# Radii.net
KiCad netlist of a schematic drawn in EAGLE
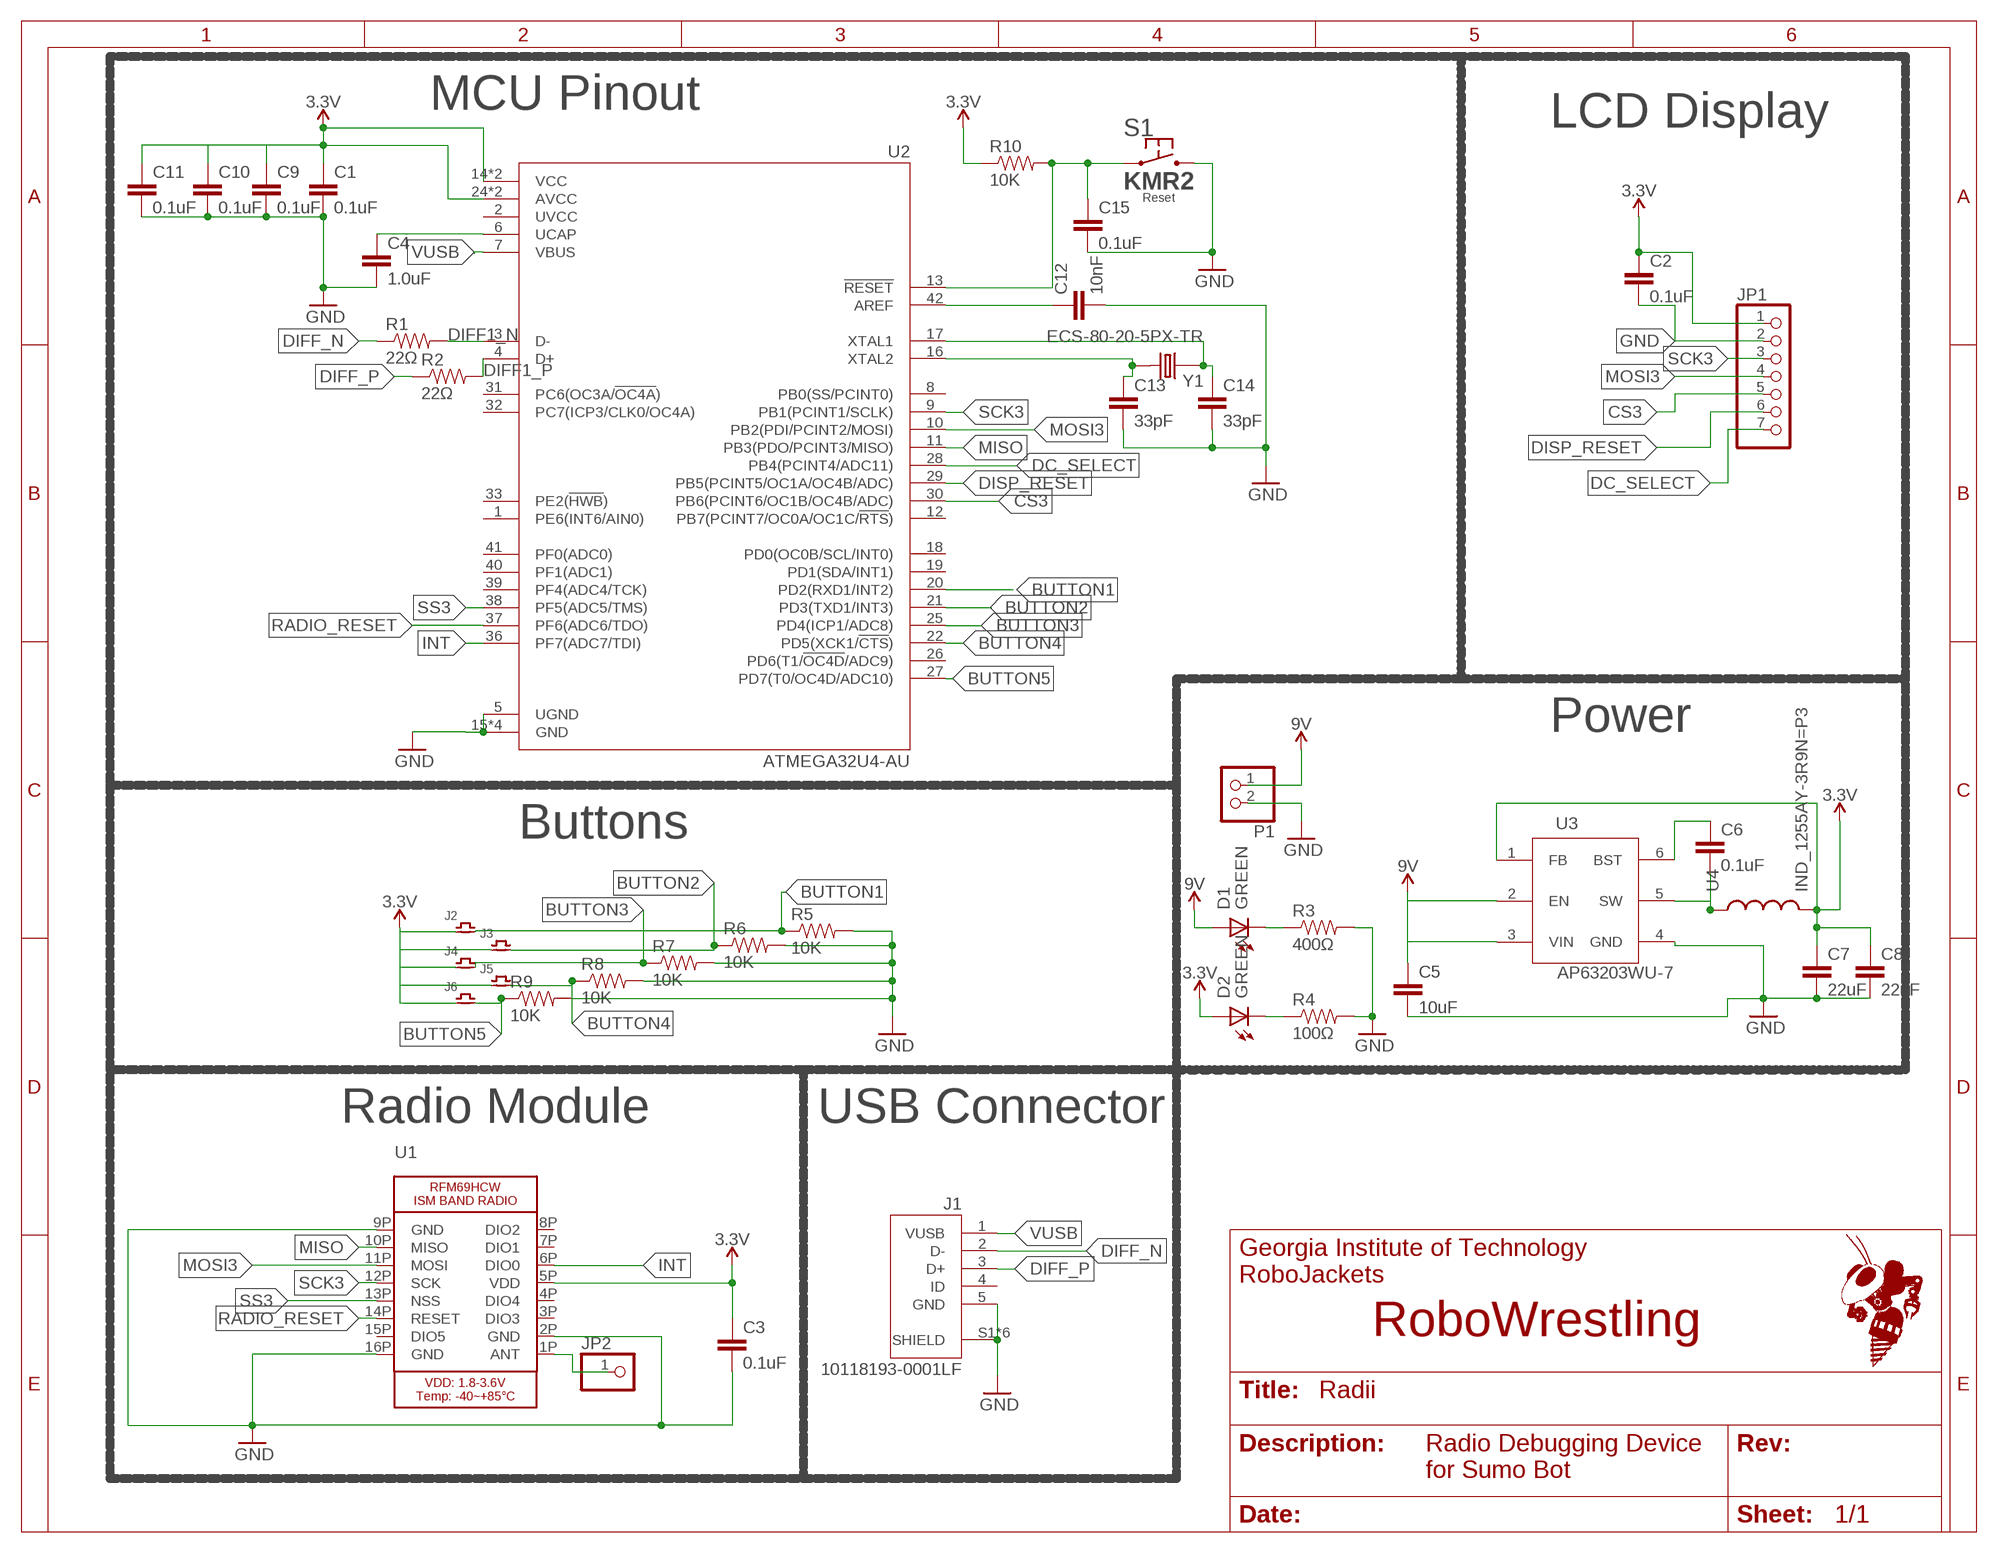
[diagram p0: schematic, sheet 1]

(export (version "E")
  (design (tool "Eeschema 10.0.6"))
  (components
    (comp (ref "C1")
      (value "0.1uF")
      (footprint "eagle-import:0603")
      (libsource (lib "eagle-import") (part "0.1UF-0603-25V-(+80/-20%)"))
    )
    (comp (ref "C2")
      (value "0.1uF")
      (footprint "eagle-import:0603")
      (libsource (lib "eagle-import") (part "0.1UF-0603-25V-(+80/-20%)"))
    )
    (comp (ref "C3")
      (value "0.1uF")
      (footprint "eagle-import:0603")
      (libsource (lib "eagle-import") (part "0.1UF-0603-25V-(+80/-20%)"))
    )
    (comp (ref "C4")
      (value "1.0uF")
      (footprint "eagle-import:0603")
      (libsource (lib "eagle-import") (part "1.0UF-0603-16V-10%"))
    )
    (comp (ref "C5")
      (value "10uF")
      (footprint "eagle-import:0603")
      (libsource (lib "eagle-import") (part "10UF-0603-6.3V-20%"))
    )
    (comp (ref "C6")
      (value "0.1uF")
      (footprint "eagle-import:0603")
      (libsource (lib "eagle-import") (part "0.1UF-0603-25V-(+80/-20%)"))
    )
    (comp (ref "C7")
      (value "22uF")
      (footprint "eagle-import:1210")
      (libsource (lib "eagle-import") (part "22UF-1210-16V-20%"))
    )
    (comp (ref "C8")
      (value "22uF")
      (footprint "eagle-import:1210")
      (libsource (lib "eagle-import") (part "22UF-1210-16V-20%"))
    )
    (comp (ref "C9")
      (value "0.1uF")
      (footprint "eagle-import:0603")
      (libsource (lib "eagle-import") (part "0.1UF-0603-25V-(+80/-20%)"))
    )
    (comp (ref "C10")
      (value "0.1uF")
      (footprint "eagle-import:0603")
      (libsource (lib "eagle-import") (part "0.1UF-0603-25V-(+80/-20%)"))
    )
    (comp (ref "C11")
      (value "0.1uF")
      (footprint "eagle-import:0603")
      (libsource (lib "eagle-import") (part "0.1UF-0603-25V-(+80/-20%)"))
    )
    (comp (ref "C12")
      (value "10nF")
      (footprint "eagle-import:0603")
      (libsource (lib "eagle-import") (part "10NF-0603-50V-10%"))
    )
    (comp (ref "C13")
      (value "33pF")
      (footprint "eagle-import:0603")
      (libsource (lib "eagle-import") (part "33PF-0603-50V-5%"))
    )
    (comp (ref "C14")
      (value "33pF")
      (footprint "eagle-import:0603")
      (libsource (lib "eagle-import") (part "33PF-0603-50V-5%"))
    )
    (comp (ref "C15")
      (value "0.1uF")
      (footprint "eagle-import:0603")
      (libsource (lib "eagle-import") (part "0.1UF-0603-25V-(+80/-20%)"))
    )
    (comp (ref "D1")
      (value "GREEN")
      (footprint "eagle-import:CHIP-LED0603")
      (libsource (lib "eagle-import") (part "LED-SMD"))
    )
    (comp (ref "D2")
      (value "GREEN")
      (footprint "eagle-import:CHIP-LED0603")
      (libsource (lib "eagle-import") (part "LED-SMD"))
    )
    (comp (ref "J1")
      (value "10118193-0001LF")
      (footprint "eagle-import:FCI_10118193-0001LF")
      (fields (field (name "DIGI-KEY_PART_NUMBER") "609-4616-1-ND") (field (name "MF") "Amphenol ICC (FCI)"))
      (libsource (lib "eagle-import") (part "10118193-0001LF"))
    )
    (comp (ref "J2")
      (value "BUTTON")
      (footprint "eagle-import:1X02")
      (libsource (lib "eagle-import") (part "BUTTON"))
    )
    (comp (ref "J3")
      (value "BUTTON")
      (footprint "eagle-import:1X02")
      (libsource (lib "eagle-import") (part "BUTTON"))
    )
    (comp (ref "J4")
      (value "BUTTON")
      (footprint "eagle-import:1X02")
      (libsource (lib "eagle-import") (part "BUTTON"))
    )
    (comp (ref "J5")
      (value "BUTTON")
      (footprint "eagle-import:1X02")
      (libsource (lib "eagle-import") (part "BUTTON"))
    )
    (comp (ref "J6")
      (value "BUTTON")
      (footprint "eagle-import:1X02")
      (libsource (lib "eagle-import") (part "BUTTON"))
    )
    (comp (ref "JP1")
      (value "PINHD-1X7")
      (footprint "eagle-import:1X07")
      (libsource (lib "eagle-import") (part "PINHD-1X7"))
    )
    (comp (ref "JP2")
      (value "PINHD-1X1")
      (footprint "eagle-import:1X01")
      (libsource (lib "eagle-import") (part "PINHD-1X1"))
    )
    (comp (ref "P1")
      (value "JST_2PIN-SMT-RA")
      (footprint "eagle-import:JST-PH-2-SMT-RA")
      (libsource (lib "eagle-import") (part "JST_2PIN-SMT-RA"))
    )
    (comp (ref "R1")
      (value "22Ω")
      (footprint "eagle-import:0603-RES")
      (libsource (lib "eagle-import") (part "22OHM1/10W1%(0603)"))
    )
    (comp (ref "R2")
      (value "22Ω")
      (footprint "eagle-import:0603-RES")
      (libsource (lib "eagle-import") (part "22OHM1/10W1%(0603)"))
    )
    (comp (ref "R3")
      (value "400Ω")
      (footprint "eagle-import:0603-RES")
      (libsource (lib "eagle-import") (part "RESISTOR0603"))
    )
    (comp (ref "R4")
      (value "100Ω")
      (footprint "eagle-import:0603-RES")
      (libsource (lib "eagle-import") (part "RESISTOR0603"))
    )
    (comp (ref "R5")
      (value "10K")
      (footprint "eagle-import:0603-RES")
      (libsource (lib "eagle-import") (part "10KOHM-1/10W-1%(0603)0603"))
    )
    (comp (ref "R6")
      (value "10K")
      (footprint "eagle-import:0603-RES")
      (libsource (lib "eagle-import") (part "10KOHM-1/10W-1%(0603)0603"))
    )
    (comp (ref "R7")
      (value "10K")
      (footprint "eagle-import:0603-RES")
      (libsource (lib "eagle-import") (part "10KOHM-1/10W-1%(0603)0603"))
    )
    (comp (ref "R8")
      (value "10K")
      (footprint "eagle-import:0603-RES")
      (libsource (lib "eagle-import") (part "10KOHM-1/10W-1%(0603)0603"))
    )
    (comp (ref "R9")
      (value "10K")
      (footprint "eagle-import:0603-RES")
      (libsource (lib "eagle-import") (part "10KOHM-1/10W-1%(0603)0603"))
    )
    (comp (ref "R10")
      (value "10K")
      (footprint "eagle-import:0603-RES")
      (libsource (lib "eagle-import") (part "10KOHM-1/10W-1%(0603)0603"))
    )
    (comp (ref "S1")
      (value "KMR2")
      (footprint "eagle-import:KMR2")
      (fields (field (name "FUNCTION") "Reset"))
      (libsource (lib "eagle-import") (part "KMR2"))
    )
    (comp (ref "U1")
      (value "RFM69HCW_SMT")
      (footprint "eagle-import:RFMHCW_SMT")
      (libsource (lib "eagle-import") (part "RFM69HCW_SMT"))
    )
    (comp (ref "U2")
      (value "ATMEGA32U4-AU")
      (footprint "eagle-import:QFP80P1200X1200X120-44N")
      (fields (field (name "MF") "Microchip") (field (name "MP") "ATMEGA32U4-AUR"))
      (libsource (lib "eagle-import") (part "ATMEGA32U4-AUR"))
    )
    (comp (ref "U3")
      (value "AP63203WU-7")
      (footprint "eagle-import:POWERREG")
      (libsource (lib "eagle-import") (part "AP63203WU-7"))
    )
    (comp (ref "U4")
      (value "IND_1255AY-3R9N=P3")
      (footprint "eagle-import:IND_1255AY-3R9N=P3")
      (libsource (lib "eagle-import") (part "IND_1255AY-3R9N=P3"))
    )
    (comp (ref "Y1")
      (value "ECS-80-20-5PX-TR")
      (footprint "eagle-import:XTAL_ECS-80-20-5PX-TR")
      (fields
        (field (name "DIGI-KEY_PART_NUMBER") "XC1271CT-ND")
        (field (name "MF") "ECS Inc.")
        (field (name "MP") "ECS-80-18-5PX-TR")
      )
      (libsource (lib "eagle-import") (part "ECS-80-20-5PX-TR"))
    )
  )
  (nets
    (net (code "1") (name "/DIFF1_N") (class "Default")
      (node (ref "R1") (pin "2") (pinfunction "2_2") (pintype "passive"))
      (node (ref "U2") (pin "3") (pinfunction "D-_3") (pintype "bidirectional"))
    )
    (net (code "2") (name "/DIFF1_P") (class "Default")
      (node (ref "R2") (pin "2") (pinfunction "2_2") (pintype "passive"))
      (node (ref "U2") (pin "4") (pinfunction "D+_4") (pintype "bidirectional"))
    )
    (net (code "3") (name "/UVCC") (class "Default")
      (node (ref "U2") (pin "2") (pinfunction "UVCC_2") (pintype "power_in"))
    )
    (net (code "4") (name "3.3V") (class "Default")
      (node (ref "C1") (pin "1") (pinfunction "1_1") (pintype "passive"))
      (node (ref "C10") (pin "1") (pinfunction "1_1") (pintype "passive"))
      (node (ref "C11") (pin "1") (pinfunction "1_1") (pintype "passive"))
      (node (ref "C2") (pin "1") (pinfunction "1_1") (pintype "passive"))
      (node (ref "C3") (pin "1") (pinfunction "1_1") (pintype "passive"))
      (node (ref "C7") (pin "1") (pinfunction "1_1") (pintype "passive"))
      (node (ref "C8") (pin "1") (pinfunction "1_1") (pintype "passive"))
      (node (ref "C9") (pin "1") (pinfunction "1_1") (pintype "passive"))
      (node (ref "D2") (pin "A") (pinfunction "A_A") (pintype "passive"))
      (node (ref "J2") (pin "1") (pinfunction "P$1_1") (pintype "bidirectional"))
      (node (ref "J3") (pin "1") (pinfunction "P$1_1") (pintype "bidirectional"))
      (node (ref "J4") (pin "1") (pinfunction "P$1_1") (pintype "bidirectional"))
      (node (ref "J5") (pin "1") (pinfunction "P$1_1") (pintype "bidirectional"))
      (node (ref "J6") (pin "1") (pinfunction "P$1_1") (pintype "bidirectional"))
      (node (ref "JP1") (pin "1") (pinfunction "1_1") (pintype "passive"))
      (node (ref "R10") (pin "1") (pinfunction "1_1") (pintype "passive"))
      (node (ref "U1") (pin "5P") (pinfunction "VDD_5P") (pintype "power_in"))
      (node (ref "U2") (pin "14") (pinfunction "VCC_14") (pintype "power_in"))
      (node (ref "U2") (pin "24") (pinfunction "AVCC_24") (pintype "power_in"))
      (node (ref "U2") (pin "34") (pinfunction "VCC_34") (pintype "power_in"))
      (node (ref "U2") (pin "44") (pinfunction "AVCC_44") (pintype "power_in"))
      (node (ref "U3") (pin "1") (pinfunction "FB_1") (pintype "bidirectional"))
      (node (ref "U4") (pin "2") (pinfunction "2_2") (pintype "passive"))
    )
    (net (code "5") (name "9V") (class "Default")
      (node (ref "C5") (pin "1") (pinfunction "1_1") (pintype "passive"))
      (node (ref "D1") (pin "A") (pinfunction "A_A") (pintype "passive"))
      (node (ref "P1") (pin "1") (pinfunction "2_1") (pintype "passive"))
      (node (ref "U3") (pin "2") (pinfunction "EN_2") (pintype "bidirectional"))
      (node (ref "U3") (pin "3") (pinfunction "VIN_3") (pintype "bidirectional"))
    )
    (net (code "6") (name "BUTTON1") (class "Default")
      (node (ref "J2") (pin "2") (pinfunction "P$2_2") (pintype "bidirectional"))
      (node (ref "R5") (pin "1") (pinfunction "1_1") (pintype "passive"))
      (node (ref "U2") (pin "20") (pinfunction "PD2(RXD1/INT2)_20") (pintype "bidirectional"))
    )
    (net (code "7") (name "BUTTON2") (class "Default")
      (node (ref "J3") (pin "2") (pinfunction "P$2_2") (pintype "bidirectional"))
      (node (ref "R6") (pin "1") (pinfunction "1_1") (pintype "passive"))
      (node (ref "U2") (pin "21") (pinfunction "PD3(TXD1/INT3)_21") (pintype "bidirectional"))
    )
    (net (code "8") (name "BUTTON3") (class "Default")
      (node (ref "J4") (pin "2") (pinfunction "P$2_2") (pintype "bidirectional"))
      (node (ref "R7") (pin "1") (pinfunction "1_1") (pintype "passive"))
      (node (ref "U2") (pin "25") (pinfunction "PD4(ICP1/ADC8)_25") (pintype "bidirectional"))
    )
    (net (code "9") (name "BUTTON4") (class "Default")
      (node (ref "J5") (pin "2") (pinfunction "P$2_2") (pintype "bidirectional"))
      (node (ref "R8") (pin "1") (pinfunction "1_1") (pintype "passive"))
      (node (ref "U2") (pin "22") (pinfunction "PD5(XCK1/~{CTS})_22") (pintype "bidirectional"))
    )
    (net (code "10") (name "BUTTON5") (class "Default")
      (node (ref "J6") (pin "2") (pinfunction "P$2_2") (pintype "bidirectional"))
      (node (ref "R9") (pin "1") (pinfunction "1_1") (pintype "passive"))
      (node (ref "U2") (pin "27") (pinfunction "PD7(T0/OC4D/ADC10)_27") (pintype "bidirectional"))
    )
    (net (code "11") (name "CS3") (class "Default")
      (node (ref "JP1") (pin "5") (pinfunction "5_5") (pintype "passive"))
      (node (ref "U2") (pin "30") (pinfunction "PB6(PCINT6/OC1B/OC4B/ADC)_30") (pintype "bidirectional"))
    )
    (net (code "12") (name "DC_SELECT") (class "Default")
      (node (ref "JP1") (pin "7") (pinfunction "7_7") (pintype "passive"))
      (node (ref "U2") (pin "28") (pinfunction "PB4(PCINT4/ADC11)_28") (pintype "bidirectional"))
    )
    (net (code "13") (name "DIFF_N") (class "Default")
      (node (ref "J1") (pin "2") (pinfunction "D-_2") (pintype "passive"))
      (node (ref "R1") (pin "1") (pinfunction "1_1") (pintype "passive"))
    )
    (net (code "14") (name "DIFF_P") (class "Default")
      (node (ref "J1") (pin "3") (pinfunction "D+_3") (pintype "passive"))
      (node (ref "R2") (pin "1") (pinfunction "1_1") (pintype "passive"))
    )
    (net (code "15") (name "DISP_RESET") (class "Default")
      (node (ref "JP1") (pin "6") (pinfunction "6_6") (pintype "passive"))
      (node (ref "U2") (pin "29") (pinfunction "PB5(PCINT5/OC1A/OC4B/ADC)_29") (pintype "bidirectional"))
    )
    (net (code "16") (name "GND") (class "Default")
      (node (ref "C1") (pin "2") (pinfunction "2_2") (pintype "passive"))
      (node (ref "C10") (pin "2") (pinfunction "2_2") (pintype "passive"))
      (node (ref "C11") (pin "2") (pinfunction "2_2") (pintype "passive"))
      (node (ref "C12") (pin "2") (pinfunction "2_2") (pintype "passive"))
      (node (ref "C13") (pin "2") (pinfunction "2_2") (pintype "passive"))
      (node (ref "C14") (pin "2") (pinfunction "2_2") (pintype "passive"))
      (node (ref "C15") (pin "2") (pinfunction "2_2") (pintype "passive"))
      (node (ref "C2") (pin "2") (pinfunction "2_2") (pintype "passive"))
      (node (ref "C3") (pin "2") (pinfunction "2_2") (pintype "passive"))
      (node (ref "C4") (pin "2") (pinfunction "2_2") (pintype "passive"))
      (node (ref "C5") (pin "2") (pinfunction "2_2") (pintype "passive"))
      (node (ref "C7") (pin "2") (pinfunction "2_2") (pintype "passive"))
      (node (ref "C8") (pin "2") (pinfunction "2_2") (pintype "passive"))
      (node (ref "C9") (pin "2") (pinfunction "2_2") (pintype "passive"))
      (node (ref "J1") (pin "5") (pinfunction "GND_5") (pintype "passive"))
      (node (ref "J1") (pin "S1") (pinfunction "SHIELD_S1") (pintype "passive"))
      (node (ref "J1") (pin "S2") (pinfunction "SHIELD_S2") (pintype "passive"))
      (node (ref "J1") (pin "S3") (pinfunction "SHIELD_S3") (pintype "passive"))
      (node (ref "J1") (pin "S4") (pinfunction "SHIELD_S4") (pintype "passive"))
      (node (ref "J1") (pin "S5") (pinfunction "SHIELD_S5") (pintype "passive"))
      (node (ref "J1") (pin "S6") (pinfunction "SHIELD_S6") (pintype "passive"))
      (node (ref "JP1") (pin "2") (pinfunction "2_2") (pintype "passive"))
      (node (ref "P1") (pin "2") (pinfunction "1_2") (pintype "passive"))
      (node (ref "R3") (pin "2") (pinfunction "2_2") (pintype "passive"))
      (node (ref "R4") (pin "2") (pinfunction "2_2") (pintype "passive"))
      (node (ref "R5") (pin "2") (pinfunction "2_2") (pintype "passive"))
      (node (ref "R6") (pin "2") (pinfunction "2_2") (pintype "passive"))
      (node (ref "R7") (pin "2") (pinfunction "2_2") (pintype "passive"))
      (node (ref "R8") (pin "2") (pinfunction "2_2") (pintype "passive"))
      (node (ref "R9") (pin "2") (pinfunction "2_2") (pintype "passive"))
      (node (ref "S1") (pin "2.1") (pinfunction "2_2.1") (pintype "passive"))
      (node (ref "S1") (pin "2.2") (pinfunction "2_2.2") (pintype "passive"))
      (node (ref "U1") (pin "16P") (pinfunction "GND_16P") (pintype "power_in"))
      (node (ref "U1") (pin "2P") (pinfunction "GND_2P") (pintype "power_in"))
      (node (ref "U1") (pin "9P") (pinfunction "GND_9P") (pintype "power_in"))
      (node (ref "U2") (pin "15") (pinfunction "GND_15") (pintype "power_in"))
      (node (ref "U2") (pin "23") (pinfunction "GND_23") (pintype "power_in"))
      (node (ref "U2") (pin "35") (pinfunction "GND_35") (pintype "power_in"))
      (node (ref "U2") (pin "43") (pinfunction "GND_43") (pintype "power_in"))
      (node (ref "U2") (pin "5") (pinfunction "UGND_5") (pintype "power_in"))
      (node (ref "U3") (pin "4") (pinfunction "GND_4") (pintype "bidirectional"))
    )
    (net (code "17") (name "INT") (class "Default")
      (node (ref "U1") (pin "6P") (pinfunction "DIO0_6P") (pintype "bidirectional"))
      (node (ref "U2") (pin "36") (pinfunction "PF7(ADC7/TDI)_36") (pintype "bidirectional"))
    )
    (net (code "18") (name "MISO") (class "Default")
      (node (ref "U1") (pin "10P") (pinfunction "MISO_10P") (pintype "output"))
      (node (ref "U2") (pin "11") (pinfunction "PB3(PDO/PCINT3/MISO)_11") (pintype "bidirectional"))
    )
    (net (code "19") (name "MOSI3") (class "Default")
      (node (ref "JP1") (pin "4") (pinfunction "4_4") (pintype "passive"))
      (node (ref "U1") (pin "11P") (pinfunction "MOSI_11P") (pintype "input"))
      (node (ref "U2") (pin "10") (pinfunction "PB2(PDI/PCINT2/MOSI)_10") (pintype "bidirectional"))
    )
    (net (code "20") (name "Net-(D1-K)") (class "Default")
      (node (ref "D1") (pin "C") (pinfunction "K_C") (pintype "passive"))
      (node (ref "R3") (pin "1") (pinfunction "1_1") (pintype "passive"))
    )
    (net (code "21") (name "Net-(D2-K)") (class "Default")
      (node (ref "D2") (pin "C") (pinfunction "K_C") (pintype "passive"))
      (node (ref "R4") (pin "1") (pinfunction "1_1") (pintype "passive"))
    )
    (net (code "22") (name "Net-(U1-ANT)") (class "Default")
      (node (ref "JP2") (pin "1") (pinfunction "1_1") (pintype "passive"))
      (node (ref "U1") (pin "1P") (pinfunction "ANT_1P") (pintype "bidirectional"))
    )
    (net (code "23") (name "Net-(U2-AREF)") (class "Default")
      (node (ref "C12") (pin "1") (pinfunction "1_1") (pintype "passive"))
      (node (ref "U2") (pin "42") (pinfunction "AREF_42") (pintype "input"))
    )
    (net (code "24") (name "Net-(U2-UCAP)") (class "Default")
      (node (ref "C4") (pin "1") (pinfunction "1_1") (pintype "passive"))
      (node (ref "U2") (pin "6") (pinfunction "UCAP_6") (pintype "power_in"))
    )
    (net (code "25") (name "Net-(U2-XTAL1)") (class "Default")
      (node (ref "C14") (pin "1") (pinfunction "1_1") (pintype "passive"))
      (node (ref "U2") (pin "17") (pinfunction "XTAL1_17") (pintype "input"))
      (node (ref "Y1") (pin "1") (pinfunction "1_1") (pintype "passive"))
    )
    (net (code "26") (name "Net-(U2-XTAL2)") (class "Default")
      (node (ref "C13") (pin "1") (pinfunction "1_1") (pintype "passive"))
      (node (ref "U2") (pin "16") (pinfunction "XTAL2_16") (pintype "output"))
      (node (ref "Y1") (pin "2") (pinfunction "2_2") (pintype "passive"))
    )
    (net (code "27") (name "Net-(U2-~{RESET})") (class "Default")
      (node (ref "C15") (pin "1") (pinfunction "1_1") (pintype "passive"))
      (node (ref "R10") (pin "2") (pinfunction "2_2") (pintype "passive"))
      (node (ref "S1") (pin "1.1") (pinfunction "1_1.1") (pintype "passive"))
      (node (ref "S1") (pin "1.2") (pinfunction "1_1.2") (pintype "passive"))
      (node (ref "U2") (pin "13") (pinfunction "~{RESET}_13") (pintype "input"))
    )
    (net (code "28") (name "Net-(U3-BST)") (class "Default")
      (node (ref "C6") (pin "1") (pinfunction "1_1") (pintype "passive"))
      (node (ref "U3") (pin "6") (pinfunction "BST_6") (pintype "bidirectional"))
    )
    (net (code "29") (name "Net-(U3-SW)") (class "Default")
      (node (ref "C6") (pin "2") (pinfunction "2_2") (pintype "passive"))
      (node (ref "U3") (pin "5") (pinfunction "SW_5") (pintype "bidirectional"))
      (node (ref "U4") (pin "1") (pinfunction "1_1") (pintype "passive"))
    )
    (net (code "30") (name "RADIO_RESET") (class "Default")
      (node (ref "U1") (pin "14P") (pinfunction "RESET_14P") (pintype "input"))
      (node (ref "U2") (pin "37") (pinfunction "PF6(ADC6/TDO)_37") (pintype "bidirectional"))
    )
    (net (code "31") (name "SCK3") (class "Default")
      (node (ref "JP1") (pin "3") (pinfunction "3_3") (pintype "passive"))
      (node (ref "U1") (pin "12P") (pinfunction "SCK_12P") (pintype "input"))
      (node (ref "U2") (pin "9") (pinfunction "PB1(PCINT1/SCLK)_9") (pintype "bidirectional"))
    )
    (net (code "32") (name "SS3") (class "Default")
      (node (ref "U1") (pin "13P") (pinfunction "NSS_13P") (pintype "input"))
      (node (ref "U2") (pin "38") (pinfunction "PF5(ADC5/TMS)_38") (pintype "bidirectional"))
    )
    (net (code "33") (name "VUSB") (class "Default")
      (node (ref "J1") (pin "1") (pinfunction "VUSB_1") (pintype "passive"))
      (node (ref "U2") (pin "7") (pinfunction "VBUS_7") (pintype "power_in"))
    )
    (net (code "34") (name "unconnected-(J1-ID-Pad4)") (class "Default")
      (node (ref "J1") (pin "4") (pinfunction "ID_4") (pintype "passive"))
    )
    (net (code "35") (name "unconnected-(U1-DIO1-Pad7P)") (class "Default")
      (node (ref "U1") (pin "7P") (pinfunction "DIO1_7P") (pintype "bidirectional"))
    )
    (net (code "36") (name "unconnected-(U1-DIO2-Pad8P)") (class "Default")
      (node (ref "U1") (pin "8P") (pinfunction "DIO2_8P") (pintype "bidirectional"))
    )
    (net (code "37") (name "unconnected-(U1-DIO3-Pad3P)") (class "Default")
      (node (ref "U1") (pin "3P") (pinfunction "DIO3_3P") (pintype "bidirectional"))
    )
    (net (code "38") (name "unconnected-(U1-DIO4-Pad4P)") (class "Default")
      (node (ref "U1") (pin "4P") (pinfunction "DIO4_4P") (pintype "bidirectional"))
    )
    (net (code "39") (name "unconnected-(U1-DIO5-Pad15P)") (class "Default")
      (node (ref "U1") (pin "15P") (pinfunction "DIO5_15P") (pintype "bidirectional"))
    )
    (net (code "40") (name "unconnected-(U2-PB0(SS{slash}PCINT0)-Pad8)") (class "Default")
      (node (ref "U2") (pin "8") (pinfunction "PB0(SS/PCINT0)_8") (pintype "bidirectional"))
    )
    (net (code "41") (name "unconnected-(U2-PB7(PCINT7{slash}OC0A{slash}OC1C{slash}~{RTS})-Pad12)") (class "Default")
      (node (ref "U2") (pin "12") (pinfunction "PB7(PCINT7/OC0A/OC1C/~{RTS})_12") (pintype "bidirectional"))
    )
    (net (code "42") (name "unconnected-(U2-PC6(OC3A{slash}~{OC4A})-Pad31)") (class "Default")
      (node (ref "U2") (pin "31") (pinfunction "PC6(OC3A/~{OC4A})_31") (pintype "bidirectional"))
    )
    (net (code "43") (name "unconnected-(U2-PC7(ICP3{slash}CLK0{slash}OC4A)-Pad32)") (class "Default")
      (node (ref "U2") (pin "32") (pinfunction "PC7(ICP3/CLK0/OC4A)_32") (pintype "bidirectional"))
    )
    (net (code "44") (name "unconnected-(U2-PD0(OC0B{slash}SCL{slash}INT0)-Pad18)") (class "Default")
      (node (ref "U2") (pin "18") (pinfunction "PD0(OC0B/SCL/INT0)_18") (pintype "bidirectional"))
    )
    (net (code "45") (name "unconnected-(U2-PD1(SDA{slash}INT1)-Pad19)") (class "Default")
      (node (ref "U2") (pin "19") (pinfunction "PD1(SDA/INT1)_19") (pintype "bidirectional"))
    )
    (net (code "46") (name "unconnected-(U2-PD6(T1{slash}~{OC4D}{slash}ADC9)-Pad26)") (class "Default")
      (node (ref "U2") (pin "26") (pinfunction "PD6(T1/~{OC4D}/ADC9)_26") (pintype "bidirectional"))
    )
    (net (code "47") (name "unconnected-(U2-PE2(~{HWB})-Pad33)") (class "Default")
      (node (ref "U2") (pin "33") (pinfunction "PE2(~{HWB})_33") (pintype "bidirectional"))
    )
    (net (code "48") (name "unconnected-(U2-PE6(INT6{slash}AIN0)-Pad1)") (class "Default")
      (node (ref "U2") (pin "1") (pinfunction "PE6(INT6/AIN0)_1") (pintype "bidirectional"))
    )
    (net (code "49") (name "unconnected-(U2-PF0(ADC0)-Pad41)") (class "Default")
      (node (ref "U2") (pin "41") (pinfunction "PF0(ADC0)_41") (pintype "bidirectional"))
    )
    (net (code "50") (name "unconnected-(U2-PF1(ADC1)-Pad40)") (class "Default")
      (node (ref "U2") (pin "40") (pinfunction "PF1(ADC1)_40") (pintype "bidirectional"))
    )
    (net (code "51") (name "unconnected-(U2-PF4(ADC4{slash}TCK)-Pad39)") (class "Default")
      (node (ref "U2") (pin "39") (pinfunction "PF4(ADC4/TCK)_39") (pintype "bidirectional"))
    )
  )
)
